# IB_VBE.net
KiCad netlist of a schematic drawn in Altium Designer
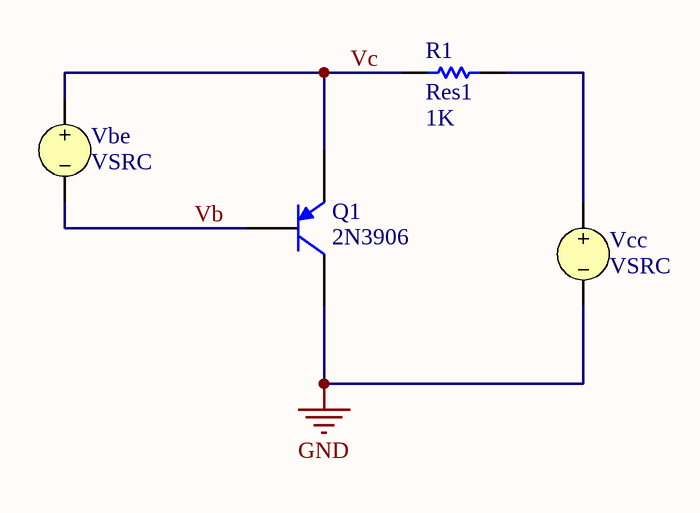
[diagram p0: IB_VBE.SchDoc]

(export (version "E")
  (design (tool "Eeschema 10.0.6"))
  (components
    (comp (ref "Q1")
      (value "2N3906")
      (footprint "TO-92A")
      (description "PNP General Purpose Amplifier")
      (fields (field (name "PUBLISHER") "Altium Limited"))
      (libsource (lib "Miscellaneous Devices") (part "2N3906"))
    )
    (comp (ref "R1")
      (value "Res1")
      (footprint "AXIAL-0.3")
      (description "Resistor")
      (fields (field (name "ALTIUM_VALUE") "1K") (field (name "PUBLISHER") "Altium Limited"))
      (libsource (lib "Miscellaneous Devices") (part "Res1"))
    )
    (comp (ref "Vbe")
      (value "VSRC")
      (description "Voltage Source")
      (fields (field (name "PUBLISHER") "Altium Limited"))
      (libsource (lib "Simulation Sources") (part "VSRC"))
    )
    (comp (ref "Vcc")
      (value "VSRC")
      (description "Voltage Source")
      (fields (field (name "PUBLISHER") "Altium Limited"))
      (libsource (lib "Simulation Sources") (part "VSRC"))
    )
  )
  (nets
    (net (code "1") (name "/Vb") (class "Default")
      (node (ref "Q1") (pin "2") (pinfunction "B_2") (pintype "passive"))
      (node (ref "Vbe") (pin "2") (pinfunction "2_2") (pintype "passive"))
    )
    (net (code "2") (name "/Vc") (class "Default")
      (node (ref "Q1") (pin "1") (pinfunction "E_1") (pintype "passive"))
      (node (ref "R1") (pin "1") (pinfunction "1_1") (pintype "passive"))
      (node (ref "Vbe") (pin "1") (pinfunction "1_1") (pintype "passive"))
    )
    (net (code "3") (name "GND") (class "Default")
      (node (ref "Q1") (pin "3") (pinfunction "C_3") (pintype "passive"))
      (node (ref "Vcc") (pin "2") (pinfunction "2_2") (pintype "passive"))
    )
    (net (code "4") (name "Net-(R1-Pad2)") (class "Default")
      (node (ref "R1") (pin "2") (pinfunction "2_2") (pintype "passive"))
      (node (ref "Vcc") (pin "1") (pinfunction "1_1") (pintype "passive"))
    )
  )
)
